# 04_LEDs.net
KiCad netlist of a schematic drawn in Altium Designer
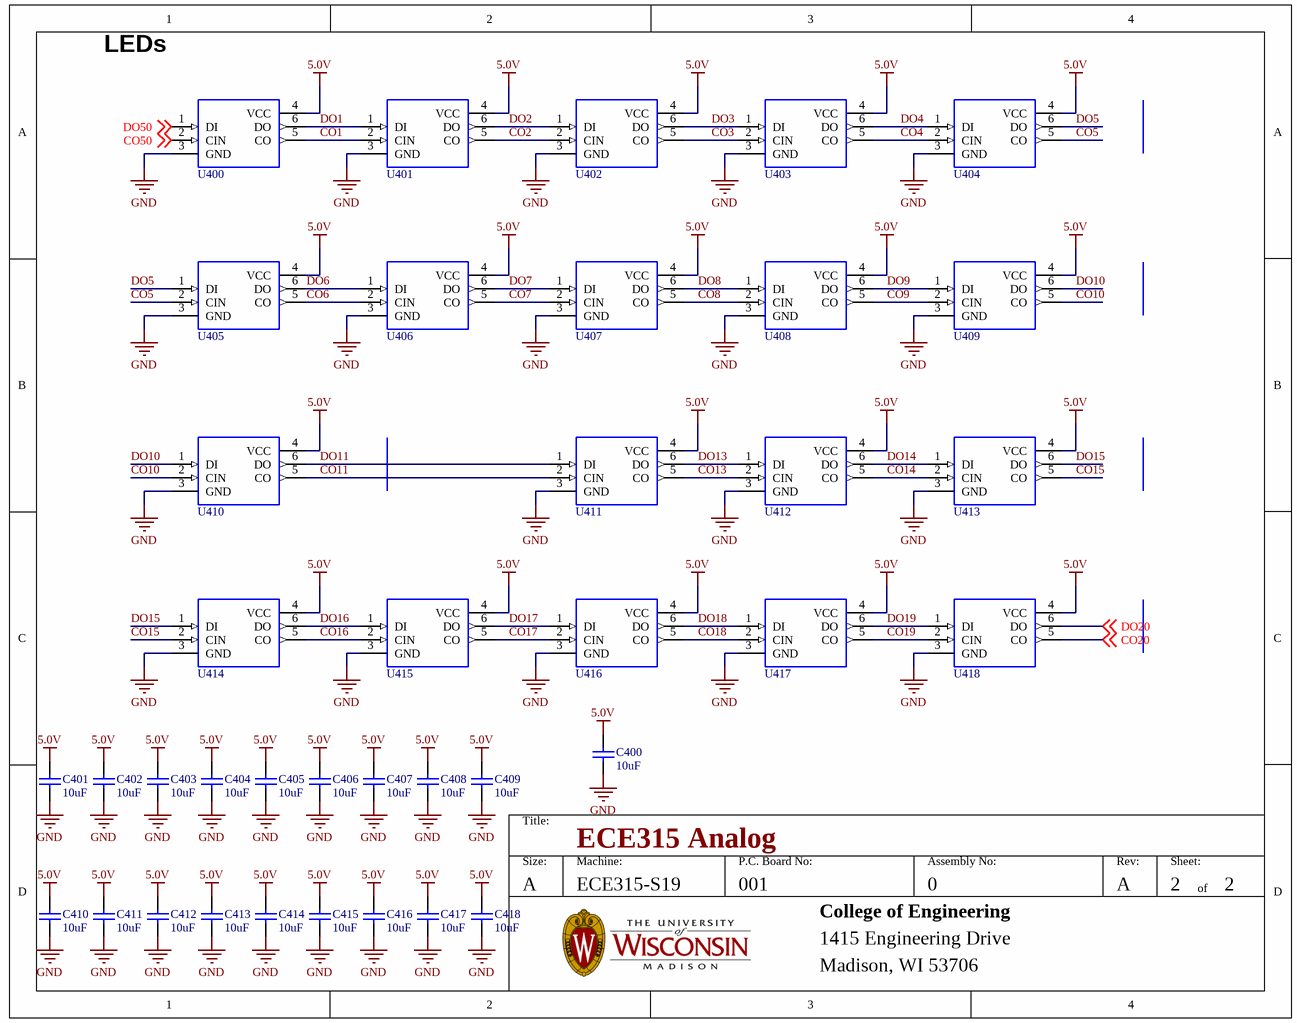
[diagram p0: 04_LEDs.SchDoc]

(export (version "E")
  (design (tool "Eeschema 10.0.6"))
  (components
    (comp (ref "C400")
      (value "10uF")
      (footprint "CAP_0805")
      (description "CAP CER 10UF 16V X7R 0805")
      (fields
        (field (name "MANUFACTURER") "Samsung")
        (field (name "MANUFACTURER PART NUMBER") "CL21A106KPCLQNC")
        (field (name "CAPACITANCE") "10uF")
      )
      (libsource (lib "ece315-2018-fall") (part "CAP_0805_U_010.00"))
    )
    (comp (ref "C401")
      (value "10uF")
      (footprint "CAP_0805")
      (description "CAP CER 10UF 16V X7R 0805")
      (fields
        (field (name "MANUFACTURER") "Samsung")
        (field (name "MANUFACTURER PART NUMBER") "CL21A106KPCLQNC")
        (field (name "CAPACITANCE") "10uF")
      )
      (libsource (lib "ece315-2018-fall") (part "CAP_0805_U_010.00"))
    )
    (comp (ref "C402")
      (value "10uF")
      (footprint "CAP_0805")
      (description "CAP CER 10UF 16V X7R 0805")
      (fields
        (field (name "MANUFACTURER") "Samsung")
        (field (name "MANUFACTURER PART NUMBER") "CL21A106KPCLQNC")
        (field (name "CAPACITANCE") "10uF")
      )
      (libsource (lib "ece315-2018-fall") (part "CAP_0805_U_010.00"))
    )
    (comp (ref "C403")
      (value "10uF")
      (footprint "CAP_0805")
      (description "CAP CER 10UF 16V X7R 0805")
      (fields
        (field (name "MANUFACTURER") "Samsung")
        (field (name "MANUFACTURER PART NUMBER") "CL21A106KPCLQNC")
        (field (name "CAPACITANCE") "10uF")
      )
      (libsource (lib "ece315-2018-fall") (part "CAP_0805_U_010.00"))
    )
    (comp (ref "C404")
      (value "10uF")
      (footprint "CAP_0805")
      (description "CAP CER 10UF 16V X7R 0805")
      (fields
        (field (name "MANUFACTURER") "Samsung")
        (field (name "MANUFACTURER PART NUMBER") "CL21A106KPCLQNC")
        (field (name "CAPACITANCE") "10uF")
      )
      (libsource (lib "ece315-2018-fall") (part "CAP_0805_U_010.00"))
    )
    (comp (ref "C405")
      (value "10uF")
      (footprint "CAP_0805")
      (description "CAP CER 10UF 16V X7R 0805")
      (fields
        (field (name "MANUFACTURER") "Samsung")
        (field (name "MANUFACTURER PART NUMBER") "CL21A106KPCLQNC")
        (field (name "CAPACITANCE") "10uF")
      )
      (libsource (lib "ece315-2018-fall") (part "CAP_0805_U_010.00"))
    )
    (comp (ref "C406")
      (value "10uF")
      (footprint "CAP_0805")
      (description "CAP CER 10UF 16V X7R 0805")
      (fields
        (field (name "MANUFACTURER") "Samsung")
        (field (name "MANUFACTURER PART NUMBER") "CL21A106KPCLQNC")
        (field (name "CAPACITANCE") "10uF")
      )
      (libsource (lib "ece315-2018-fall") (part "CAP_0805_U_010.00"))
    )
    (comp (ref "C407")
      (value "10uF")
      (footprint "CAP_0805")
      (description "CAP CER 10UF 16V X7R 0805")
      (fields
        (field (name "MANUFACTURER") "Samsung")
        (field (name "MANUFACTURER PART NUMBER") "CL21A106KPCLQNC")
        (field (name "CAPACITANCE") "10uF")
      )
      (libsource (lib "ece315-2018-fall") (part "CAP_0805_U_010.00"))
    )
    (comp (ref "C408")
      (value "10uF")
      (footprint "CAP_0805")
      (description "CAP CER 10UF 16V X7R 0805")
      (fields
        (field (name "MANUFACTURER") "Samsung")
        (field (name "MANUFACTURER PART NUMBER") "CL21A106KPCLQNC")
        (field (name "CAPACITANCE") "10uF")
      )
      (libsource (lib "ece315-2018-fall") (part "CAP_0805_U_010.00"))
    )
    (comp (ref "C409")
      (value "10uF")
      (footprint "CAP_0805")
      (description "CAP CER 10UF 16V X7R 0805")
      (fields
        (field (name "MANUFACTURER") "Samsung")
        (field (name "MANUFACTURER PART NUMBER") "CL21A106KPCLQNC")
        (field (name "CAPACITANCE") "10uF")
      )
      (libsource (lib "ece315-2018-fall") (part "CAP_0805_U_010.00"))
    )
    (comp (ref "C410")
      (value "10uF")
      (footprint "CAP_0805")
      (description "CAP CER 10UF 16V X7R 0805")
      (fields
        (field (name "MANUFACTURER") "Samsung")
        (field (name "MANUFACTURER PART NUMBER") "CL21A106KPCLQNC")
        (field (name "CAPACITANCE") "10uF")
      )
      (libsource (lib "ece315-2018-fall") (part "CAP_0805_U_010.00"))
    )
    (comp (ref "C411")
      (value "10uF")
      (footprint "CAP_0805")
      (description "CAP CER 10UF 16V X7R 0805")
      (fields
        (field (name "MANUFACTURER") "Samsung")
        (field (name "MANUFACTURER PART NUMBER") "CL21A106KPCLQNC")
        (field (name "CAPACITANCE") "10uF")
      )
      (libsource (lib "ece315-2018-fall") (part "CAP_0805_U_010.00"))
    )
    (comp (ref "C412")
      (value "10uF")
      (footprint "CAP_0805")
      (description "CAP CER 10UF 16V X7R 0805")
      (fields
        (field (name "MANUFACTURER") "Samsung")
        (field (name "MANUFACTURER PART NUMBER") "CL21A106KPCLQNC")
        (field (name "CAPACITANCE") "10uF")
      )
      (libsource (lib "ece315-2018-fall") (part "CAP_0805_U_010.00"))
    )
    (comp (ref "C413")
      (value "10uF")
      (footprint "CAP_0805")
      (description "CAP CER 10UF 16V X7R 0805")
      (fields
        (field (name "MANUFACTURER") "Samsung")
        (field (name "MANUFACTURER PART NUMBER") "CL21A106KPCLQNC")
        (field (name "CAPACITANCE") "10uF")
      )
      (libsource (lib "ece315-2018-fall") (part "CAP_0805_U_010.00"))
    )
    (comp (ref "C414")
      (value "10uF")
      (footprint "CAP_0805")
      (description "CAP CER 10UF 16V X7R 0805")
      (fields
        (field (name "MANUFACTURER") "Samsung")
        (field (name "MANUFACTURER PART NUMBER") "CL21A106KPCLQNC")
        (field (name "CAPACITANCE") "10uF")
      )
      (libsource (lib "ece315-2018-fall") (part "CAP_0805_U_010.00"))
    )
    (comp (ref "C415")
      (value "10uF")
      (footprint "CAP_0805")
      (description "CAP CER 10UF 16V X7R 0805")
      (fields
        (field (name "MANUFACTURER") "Samsung")
        (field (name "MANUFACTURER PART NUMBER") "CL21A106KPCLQNC")
        (field (name "CAPACITANCE") "10uF")
      )
      (libsource (lib "ece315-2018-fall") (part "CAP_0805_U_010.00"))
    )
    (comp (ref "C416")
      (value "10uF")
      (footprint "CAP_0805")
      (description "CAP CER 10UF 16V X7R 0805")
      (fields
        (field (name "MANUFACTURER") "Samsung")
        (field (name "MANUFACTURER PART NUMBER") "CL21A106KPCLQNC")
        (field (name "CAPACITANCE") "10uF")
      )
      (libsource (lib "ece315-2018-fall") (part "CAP_0805_U_010.00"))
    )
    (comp (ref "C417")
      (value "10uF")
      (footprint "CAP_0805")
      (description "CAP CER 10UF 16V X7R 0805")
      (fields
        (field (name "MANUFACTURER") "Samsung")
        (field (name "MANUFACTURER PART NUMBER") "CL21A106KPCLQNC")
        (field (name "CAPACITANCE") "10uF")
      )
      (libsource (lib "ece315-2018-fall") (part "CAP_0805_U_010.00"))
    )
    (comp (ref "C418")
      (value "10uF")
      (footprint "CAP_0805")
      (description "CAP CER 10UF 16V X7R 0805")
      (fields
        (field (name "MANUFACTURER") "Samsung")
        (field (name "MANUFACTURER PART NUMBER") "CL21A106KPCLQNC")
        (field (name "CAPACITANCE") "10uF")
      )
      (libsource (lib "ece315-2018-fall") (part "CAP_0805_U_010.00"))
    )
    (comp (ref "U400")
      (value "IC_APA102C")
      (footprint "APA102C")
      (description "APA102C LED")
      (libsource (lib "ece315-2018-fall") (part "IC_APA102C"))
    )
    (comp (ref "U401")
      (value "IC_APA102C")
      (footprint "APA102C")
      (description "APA102C LED")
      (libsource (lib "ece315-2018-fall") (part "IC_APA102C"))
    )
    (comp (ref "U402")
      (value "IC_APA102C")
      (footprint "APA102C")
      (description "APA102C LED")
      (libsource (lib "ece315-2018-fall") (part "IC_APA102C"))
    )
    (comp (ref "U403")
      (value "IC_APA102C")
      (footprint "APA102C")
      (description "APA102C LED")
      (libsource (lib "ece315-2018-fall") (part "IC_APA102C"))
    )
    (comp (ref "U404")
      (value "IC_APA102C")
      (footprint "APA102C")
      (description "APA102C LED")
      (libsource (lib "ece315-2018-fall") (part "IC_APA102C"))
    )
    (comp (ref "U405")
      (value "IC_APA102C")
      (footprint "APA102C")
      (description "APA102C LED")
      (libsource (lib "ece315-2018-fall") (part "IC_APA102C"))
    )
    (comp (ref "U406")
      (value "IC_APA102C")
      (footprint "APA102C")
      (description "APA102C LED")
      (libsource (lib "ece315-2018-fall") (part "IC_APA102C"))
    )
    (comp (ref "U407")
      (value "IC_APA102C")
      (footprint "APA102C")
      (description "APA102C LED")
      (libsource (lib "ece315-2018-fall") (part "IC_APA102C"))
    )
    (comp (ref "U408")
      (value "IC_APA102C")
      (footprint "APA102C")
      (description "APA102C LED")
      (libsource (lib "ece315-2018-fall") (part "IC_APA102C"))
    )
    (comp (ref "U409")
      (value "IC_APA102C")
      (footprint "APA102C")
      (description "APA102C LED")
      (libsource (lib "ece315-2018-fall") (part "IC_APA102C"))
    )
    (comp (ref "U410")
      (value "IC_APA102C")
      (footprint "APA102C")
      (description "APA102C LED")
      (libsource (lib "ece315-2018-fall") (part "IC_APA102C"))
    )
    (comp (ref "U411")
      (value "IC_APA102C")
      (footprint "APA102C")
      (description "APA102C LED")
      (libsource (lib "ece315-2018-fall") (part "IC_APA102C"))
    )
    (comp (ref "U412")
      (value "IC_APA102C")
      (footprint "APA102C")
      (description "APA102C LED")
      (libsource (lib "ece315-2018-fall") (part "IC_APA102C"))
    )
    (comp (ref "U413")
      (value "IC_APA102C")
      (footprint "APA102C")
      (description "APA102C LED")
      (libsource (lib "ece315-2018-fall") (part "IC_APA102C"))
    )
    (comp (ref "U414")
      (value "IC_APA102C")
      (footprint "APA102C")
      (description "APA102C LED")
      (libsource (lib "ece315-2018-fall") (part "IC_APA102C"))
    )
    (comp (ref "U415")
      (value "IC_APA102C")
      (footprint "APA102C")
      (description "APA102C LED")
      (libsource (lib "ece315-2018-fall") (part "IC_APA102C"))
    )
    (comp (ref "U416")
      (value "IC_APA102C")
      (footprint "APA102C")
      (description "APA102C LED")
      (libsource (lib "ece315-2018-fall") (part "IC_APA102C"))
    )
    (comp (ref "U417")
      (value "IC_APA102C")
      (footprint "APA102C")
      (description "APA102C LED")
      (libsource (lib "ece315-2018-fall") (part "IC_APA102C"))
    )
    (comp (ref "U418")
      (value "IC_APA102C")
      (footprint "APA102C")
      (description "APA102C LED")
      (libsource (lib "ece315-2018-fall") (part "IC_APA102C"))
    )
  )
  (nets
    (net (code "1") (name "/CO1") (class "Default")
      (node (ref "U400") (pin "5") (pinfunction "CO_5") (pintype "output"))
      (node (ref "U401") (pin "2") (pinfunction "CIN_2") (pintype "input"))
    )
    (net (code "2") (name "/CO2") (class "Default")
      (node (ref "U401") (pin "5") (pinfunction "CO_5") (pintype "output"))
      (node (ref "U402") (pin "2") (pinfunction "CIN_2") (pintype "input"))
    )
    (net (code "3") (name "/CO3") (class "Default")
      (node (ref "U402") (pin "5") (pinfunction "CO_5") (pintype "output"))
      (node (ref "U403") (pin "2") (pinfunction "CIN_2") (pintype "input"))
    )
    (net (code "4") (name "/CO4") (class "Default")
      (node (ref "U403") (pin "5") (pinfunction "CO_5") (pintype "output"))
      (node (ref "U404") (pin "2") (pinfunction "CIN_2") (pintype "input"))
    )
    (net (code "5") (name "/CO5") (class "Default")
      (node (ref "U404") (pin "5") (pinfunction "CO_5") (pintype "output"))
      (node (ref "U405") (pin "2") (pinfunction "CIN_2") (pintype "input"))
    )
    (net (code "6") (name "/CO6") (class "Default")
      (node (ref "U405") (pin "5") (pinfunction "CO_5") (pintype "output"))
      (node (ref "U406") (pin "2") (pinfunction "CIN_2") (pintype "input"))
    )
    (net (code "7") (name "/CO7") (class "Default")
      (node (ref "U406") (pin "5") (pinfunction "CO_5") (pintype "output"))
      (node (ref "U407") (pin "2") (pinfunction "CIN_2") (pintype "input"))
    )
    (net (code "8") (name "/CO8") (class "Default")
      (node (ref "U407") (pin "5") (pinfunction "CO_5") (pintype "output"))
      (node (ref "U408") (pin "2") (pinfunction "CIN_2") (pintype "input"))
    )
    (net (code "9") (name "/CO9") (class "Default")
      (node (ref "U408") (pin "5") (pinfunction "CO_5") (pintype "output"))
      (node (ref "U409") (pin "2") (pinfunction "CIN_2") (pintype "input"))
    )
    (net (code "10") (name "/CO10") (class "Default")
      (node (ref "U409") (pin "5") (pinfunction "CO_5") (pintype "output"))
      (node (ref "U410") (pin "2") (pinfunction "CIN_2") (pintype "input"))
    )
    (net (code "11") (name "/CO11") (class "Default")
      (node (ref "U410") (pin "5") (pinfunction "CO_5") (pintype "output"))
      (node (ref "U411") (pin "2") (pinfunction "CIN_2") (pintype "input"))
    )
    (net (code "12") (name "/CO13") (class "Default")
      (node (ref "U411") (pin "5") (pinfunction "CO_5") (pintype "output"))
      (node (ref "U412") (pin "2") (pinfunction "CIN_2") (pintype "input"))
    )
    (net (code "13") (name "/CO14") (class "Default")
      (node (ref "U412") (pin "5") (pinfunction "CO_5") (pintype "output"))
      (node (ref "U413") (pin "2") (pinfunction "CIN_2") (pintype "input"))
    )
    (net (code "14") (name "/CO15") (class "Default")
      (node (ref "U413") (pin "5") (pinfunction "CO_5") (pintype "output"))
      (node (ref "U414") (pin "2") (pinfunction "CIN_2") (pintype "input"))
    )
    (net (code "15") (name "/CO16") (class "Default")
      (node (ref "U414") (pin "5") (pinfunction "CO_5") (pintype "output"))
      (node (ref "U415") (pin "2") (pinfunction "CIN_2") (pintype "input"))
    )
    (net (code "16") (name "/CO17") (class "Default")
      (node (ref "U415") (pin "5") (pinfunction "CO_5") (pintype "output"))
      (node (ref "U416") (pin "2") (pinfunction "CIN_2") (pintype "input"))
    )
    (net (code "17") (name "/CO18") (class "Default")
      (node (ref "U416") (pin "5") (pinfunction "CO_5") (pintype "output"))
      (node (ref "U417") (pin "2") (pinfunction "CIN_2") (pintype "input"))
    )
    (net (code "18") (name "/CO19") (class "Default")
      (node (ref "U417") (pin "5") (pinfunction "CO_5") (pintype "output"))
      (node (ref "U418") (pin "2") (pinfunction "CIN_2") (pintype "input"))
    )
    (net (code "19") (name "/DO1") (class "Default")
      (node (ref "U400") (pin "6") (pinfunction "DO_6") (pintype "output"))
      (node (ref "U401") (pin "1") (pinfunction "DI_1") (pintype "input"))
    )
    (net (code "20") (name "/DO2") (class "Default")
      (node (ref "U401") (pin "6") (pinfunction "DO_6") (pintype "output"))
      (node (ref "U402") (pin "1") (pinfunction "DI_1") (pintype "input"))
    )
    (net (code "21") (name "/DO3") (class "Default")
      (node (ref "U402") (pin "6") (pinfunction "DO_6") (pintype "output"))
      (node (ref "U403") (pin "1") (pinfunction "DI_1") (pintype "input"))
    )
    (net (code "22") (name "/DO4") (class "Default")
      (node (ref "U403") (pin "6") (pinfunction "DO_6") (pintype "output"))
      (node (ref "U404") (pin "1") (pinfunction "DI_1") (pintype "input"))
    )
    (net (code "23") (name "/DO5") (class "Default")
      (node (ref "U404") (pin "6") (pinfunction "DO_6") (pintype "output"))
      (node (ref "U405") (pin "1") (pinfunction "DI_1") (pintype "input"))
    )
    (net (code "24") (name "/DO6") (class "Default")
      (node (ref "U405") (pin "6") (pinfunction "DO_6") (pintype "output"))
      (node (ref "U406") (pin "1") (pinfunction "DI_1") (pintype "input"))
    )
    (net (code "25") (name "/DO7") (class "Default")
      (node (ref "U406") (pin "6") (pinfunction "DO_6") (pintype "output"))
      (node (ref "U407") (pin "1") (pinfunction "DI_1") (pintype "input"))
    )
    (net (code "26") (name "/DO8") (class "Default")
      (node (ref "U407") (pin "6") (pinfunction "DO_6") (pintype "output"))
      (node (ref "U408") (pin "1") (pinfunction "DI_1") (pintype "input"))
    )
    (net (code "27") (name "/DO9") (class "Default")
      (node (ref "U408") (pin "6") (pinfunction "DO_6") (pintype "output"))
      (node (ref "U409") (pin "1") (pinfunction "DI_1") (pintype "input"))
    )
    (net (code "28") (name "/DO10") (class "Default")
      (node (ref "U409") (pin "6") (pinfunction "DO_6") (pintype "output"))
      (node (ref "U410") (pin "1") (pinfunction "DI_1") (pintype "input"))
    )
    (net (code "29") (name "/DO11") (class "Default")
      (node (ref "U410") (pin "6") (pinfunction "DO_6") (pintype "output"))
      (node (ref "U411") (pin "1") (pinfunction "DI_1") (pintype "input"))
    )
    (net (code "30") (name "/DO13") (class "Default")
      (node (ref "U411") (pin "6") (pinfunction "DO_6") (pintype "output"))
      (node (ref "U412") (pin "1") (pinfunction "DI_1") (pintype "input"))
    )
    (net (code "31") (name "/DO14") (class "Default")
      (node (ref "U412") (pin "6") (pinfunction "DO_6") (pintype "output"))
      (node (ref "U413") (pin "1") (pinfunction "DI_1") (pintype "input"))
    )
    (net (code "32") (name "/DO15") (class "Default")
      (node (ref "U413") (pin "6") (pinfunction "DO_6") (pintype "output"))
      (node (ref "U414") (pin "1") (pinfunction "DI_1") (pintype "input"))
    )
    (net (code "33") (name "/DO16") (class "Default")
      (node (ref "U414") (pin "6") (pinfunction "DO_6") (pintype "output"))
      (node (ref "U415") (pin "1") (pinfunction "DI_1") (pintype "input"))
    )
    (net (code "34") (name "/DO17") (class "Default")
      (node (ref "U415") (pin "6") (pinfunction "DO_6") (pintype "output"))
      (node (ref "U416") (pin "1") (pinfunction "DI_1") (pintype "input"))
    )
    (net (code "35") (name "/DO18") (class "Default")
      (node (ref "U416") (pin "6") (pinfunction "DO_6") (pintype "output"))
      (node (ref "U417") (pin "1") (pinfunction "DI_1") (pintype "input"))
    )
    (net (code "36") (name "/DO19") (class "Default")
      (node (ref "U417") (pin "6") (pinfunction "DO_6") (pintype "output"))
      (node (ref "U418") (pin "1") (pinfunction "DI_1") (pintype "input"))
    )
    (net (code "37") (name "5.0V") (class "Default")
      (node (ref "C400") (pin "2") (pinfunction "2_2") (pintype "passive"))
      (node (ref "C401") (pin "2") (pinfunction "2_2") (pintype "passive"))
      (node (ref "C402") (pin "2") (pinfunction "2_2") (pintype "passive"))
      (node (ref "C403") (pin "2") (pinfunction "2_2") (pintype "passive"))
      (node (ref "C404") (pin "2") (pinfunction "2_2") (pintype "passive"))
      (node (ref "C405") (pin "2") (pinfunction "2_2") (pintype "passive"))
      (node (ref "C406") (pin "2") (pinfunction "2_2") (pintype "passive"))
      (node (ref "C407") (pin "2") (pinfunction "2_2") (pintype "passive"))
      (node (ref "C408") (pin "2") (pinfunction "2_2") (pintype "passive"))
      (node (ref "C409") (pin "2") (pinfunction "2_2") (pintype "passive"))
      (node (ref "C410") (pin "2") (pinfunction "2_2") (pintype "passive"))
      (node (ref "C411") (pin "2") (pinfunction "2_2") (pintype "passive"))
      (node (ref "C412") (pin "2") (pinfunction "2_2") (pintype "passive"))
      (node (ref "C413") (pin "2") (pinfunction "2_2") (pintype "passive"))
      (node (ref "C414") (pin "2") (pinfunction "2_2") (pintype "passive"))
      (node (ref "C415") (pin "2") (pinfunction "2_2") (pintype "passive"))
      (node (ref "C416") (pin "2") (pinfunction "2_2") (pintype "passive"))
      (node (ref "C417") (pin "2") (pinfunction "2_2") (pintype "passive"))
      (node (ref "C418") (pin "2") (pinfunction "2_2") (pintype "passive"))
      (node (ref "U400") (pin "4") (pinfunction "VCC_4") (pintype "power_in"))
      (node (ref "U401") (pin "4") (pinfunction "VCC_4") (pintype "power_in"))
      (node (ref "U402") (pin "4") (pinfunction "VCC_4") (pintype "power_in"))
      (node (ref "U403") (pin "4") (pinfunction "VCC_4") (pintype "power_in"))
      (node (ref "U404") (pin "4") (pinfunction "VCC_4") (pintype "power_in"))
      (node (ref "U405") (pin "4") (pinfunction "VCC_4") (pintype "power_in"))
      (node (ref "U406") (pin "4") (pinfunction "VCC_4") (pintype "power_in"))
      (node (ref "U407") (pin "4") (pinfunction "VCC_4") (pintype "power_in"))
      (node (ref "U408") (pin "4") (pinfunction "VCC_4") (pintype "power_in"))
      (node (ref "U409") (pin "4") (pinfunction "VCC_4") (pintype "power_in"))
      (node (ref "U410") (pin "4") (pinfunction "VCC_4") (pintype "power_in"))
      (node (ref "U411") (pin "4") (pinfunction "VCC_4") (pintype "power_in"))
      (node (ref "U412") (pin "4") (pinfunction "VCC_4") (pintype "power_in"))
      (node (ref "U413") (pin "4") (pinfunction "VCC_4") (pintype "power_in"))
      (node (ref "U414") (pin "4") (pinfunction "VCC_4") (pintype "power_in"))
      (node (ref "U415") (pin "4") (pinfunction "VCC_4") (pintype "power_in"))
      (node (ref "U416") (pin "4") (pinfunction "VCC_4") (pintype "power_in"))
      (node (ref "U417") (pin "4") (pinfunction "VCC_4") (pintype "power_in"))
      (node (ref "U418") (pin "4") (pinfunction "VCC_4") (pintype "power_in"))
    )
    (net (code "38") (name "CO20") (class "Default")
      (node (ref "U418") (pin "5") (pinfunction "CO_5") (pintype "output"))
    )
    (net (code "39") (name "CO50") (class "Default")
      (node (ref "U400") (pin "2") (pinfunction "CIN_2") (pintype "input"))
    )
    (net (code "40") (name "DO20") (class "Default")
      (node (ref "U418") (pin "6") (pinfunction "DO_6") (pintype "output"))
    )
    (net (code "41") (name "DO50") (class "Default")
      (node (ref "U400") (pin "1") (pinfunction "DI_1") (pintype "input"))
    )
    (net (code "42") (name "GND") (class "Default")
      (node (ref "C400") (pin "1") (pinfunction "1_1") (pintype "passive"))
      (node (ref "C401") (pin "1") (pinfunction "1_1") (pintype "passive"))
      (node (ref "C402") (pin "1") (pinfunction "1_1") (pintype "passive"))
      (node (ref "C403") (pin "1") (pinfunction "1_1") (pintype "passive"))
      (node (ref "C404") (pin "1") (pinfunction "1_1") (pintype "passive"))
      (node (ref "C405") (pin "1") (pinfunction "1_1") (pintype "passive"))
      (node (ref "C406") (pin "1") (pinfunction "1_1") (pintype "passive"))
      (node (ref "C407") (pin "1") (pinfunction "1_1") (pintype "passive"))
      (node (ref "C408") (pin "1") (pinfunction "1_1") (pintype "passive"))
      (node (ref "C409") (pin "1") (pinfunction "1_1") (pintype "passive"))
      (node (ref "C410") (pin "1") (pinfunction "1_1") (pintype "passive"))
      (node (ref "C411") (pin "1") (pinfunction "1_1") (pintype "passive"))
      (node (ref "C412") (pin "1") (pinfunction "1_1") (pintype "passive"))
      (node (ref "C413") (pin "1") (pinfunction "1_1") (pintype "passive"))
      (node (ref "C414") (pin "1") (pinfunction "1_1") (pintype "passive"))
      (node (ref "C415") (pin "1") (pinfunction "1_1") (pintype "passive"))
      (node (ref "C416") (pin "1") (pinfunction "1_1") (pintype "passive"))
      (node (ref "C417") (pin "1") (pinfunction "1_1") (pintype "passive"))
      (node (ref "C418") (pin "1") (pinfunction "1_1") (pintype "passive"))
      (node (ref "U400") (pin "3") (pinfunction "GND_3") (pintype "power_in"))
      (node (ref "U401") (pin "3") (pinfunction "GND_3") (pintype "power_in"))
      (node (ref "U402") (pin "3") (pinfunction "GND_3") (pintype "power_in"))
      (node (ref "U403") (pin "3") (pinfunction "GND_3") (pintype "power_in"))
      (node (ref "U404") (pin "3") (pinfunction "GND_3") (pintype "power_in"))
      (node (ref "U405") (pin "3") (pinfunction "GND_3") (pintype "power_in"))
      (node (ref "U406") (pin "3") (pinfunction "GND_3") (pintype "power_in"))
      (node (ref "U407") (pin "3") (pinfunction "GND_3") (pintype "power_in"))
      (node (ref "U408") (pin "3") (pinfunction "GND_3") (pintype "power_in"))
      (node (ref "U409") (pin "3") (pinfunction "GND_3") (pintype "power_in"))
      (node (ref "U410") (pin "3") (pinfunction "GND_3") (pintype "power_in"))
      (node (ref "U411") (pin "3") (pinfunction "GND_3") (pintype "power_in"))
      (node (ref "U412") (pin "3") (pinfunction "GND_3") (pintype "power_in"))
      (node (ref "U413") (pin "3") (pinfunction "GND_3") (pintype "power_in"))
      (node (ref "U414") (pin "3") (pinfunction "GND_3") (pintype "power_in"))
      (node (ref "U415") (pin "3") (pinfunction "GND_3") (pintype "power_in"))
      (node (ref "U416") (pin "3") (pinfunction "GND_3") (pintype "power_in"))
      (node (ref "U417") (pin "3") (pinfunction "GND_3") (pintype "power_in"))
      (node (ref "U418") (pin "3") (pinfunction "GND_3") (pintype "power_in"))
    )
  )
)
